# P06_USB.net
KiCad netlist of a schematic drawn in Altium Designer
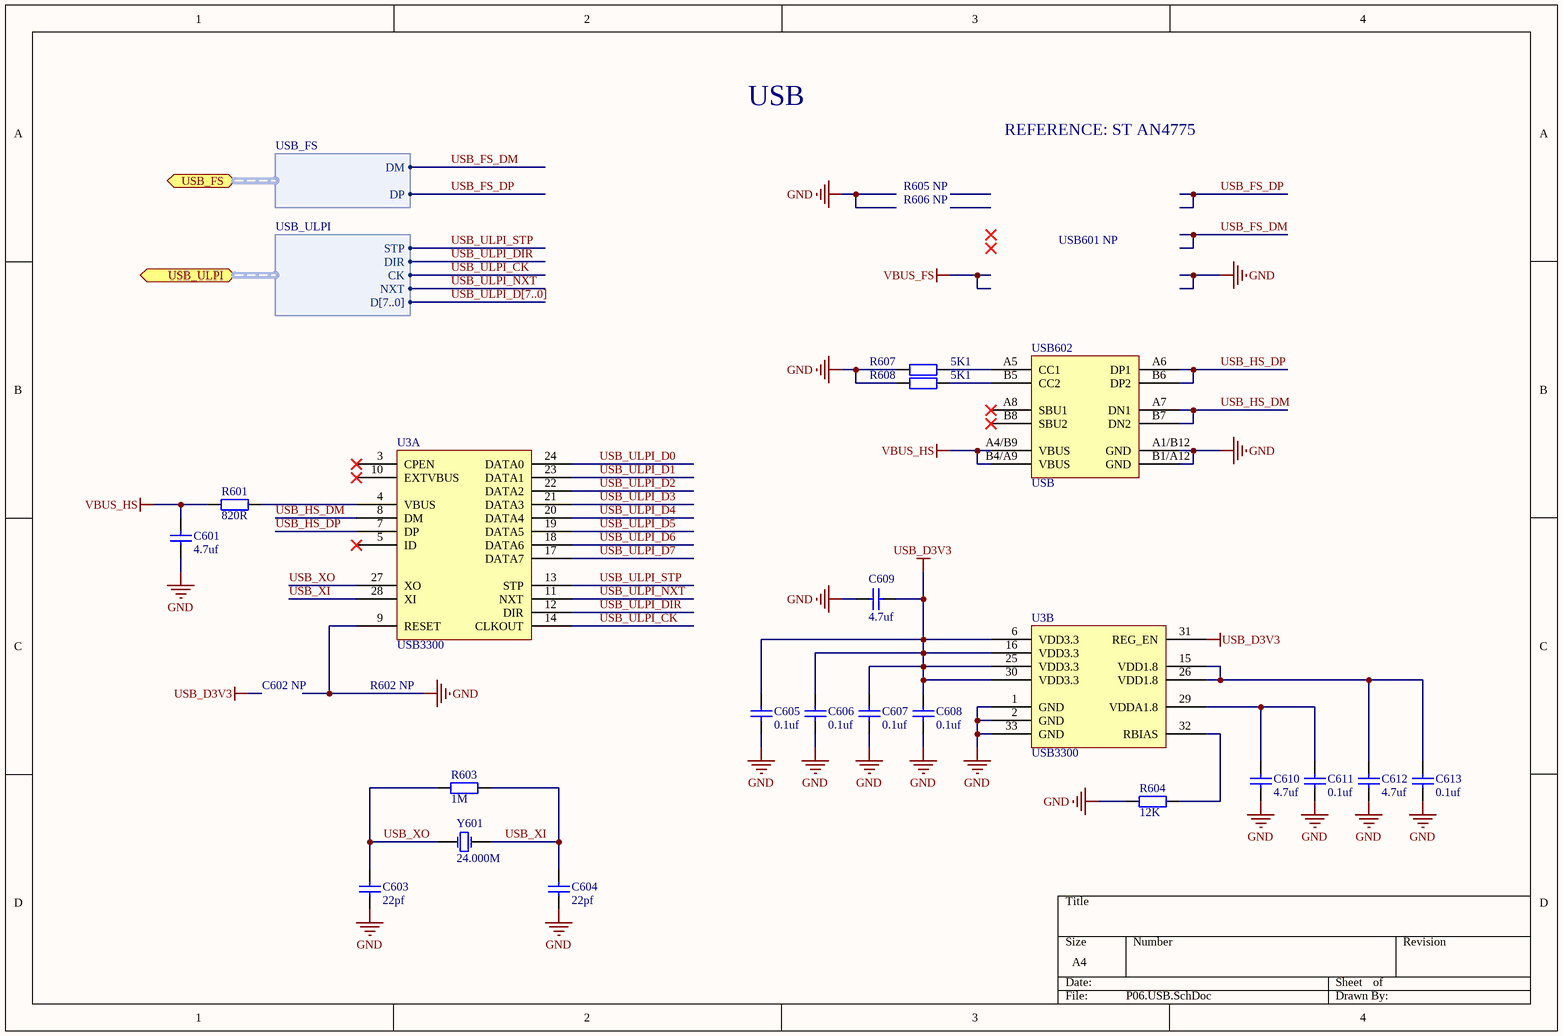
[diagram p0: P06.USB.SchDoc]

(export (version "E")
  (design (tool "Eeschema 10.0.6"))
  (components
    (comp (ref "C601")
      (value "4.7uf")
      (footprint "C0603")
      (fields (field (name "Comment") "Cap"))
      (libsource (lib "carrot_lib") (part "Cap"))
    )
    (comp (ref "C603")
      (value "22pf")
      (footprint "C0603")
      (fields (field (name "Comment") "Cap"))
      (libsource (lib "carrot_lib") (part "Cap"))
    )
    (comp (ref "C604")
      (value "22pf")
      (footprint "C0603")
      (fields (field (name "Comment") "Cap"))
      (libsource (lib "carrot_lib") (part "Cap"))
    )
    (comp (ref "C605")
      (value "0.1uf")
      (footprint "C0402")
      (fields (field (name "Comment") "Cap"))
      (libsource (lib "carrot_lib") (part "Cap"))
    )
    (comp (ref "C606")
      (value "0.1uf")
      (footprint "C0402")
      (fields (field (name "Comment") "Cap"))
      (libsource (lib "carrot_lib") (part "Cap"))
    )
    (comp (ref "C607")
      (value "0.1uf")
      (footprint "C0402")
      (fields (field (name "Comment") "Cap"))
      (libsource (lib "carrot_lib") (part "Cap"))
    )
    (comp (ref "C608")
      (value "0.1uf")
      (footprint "C0402")
      (fields (field (name "Comment") "Cap"))
      (libsource (lib "carrot_lib") (part "Cap"))
    )
    (comp (ref "C609")
      (value "4.7uf")
      (footprint "C0603")
      (fields (field (name "Comment") "Cap"))
      (libsource (lib "carrot_lib") (part "Cap"))
    )
    (comp (ref "C610")
      (value "4.7uf")
      (footprint "C0402")
      (fields (field (name "Comment") "Cap"))
      (libsource (lib "carrot_lib") (part "Cap"))
    )
    (comp (ref "C611")
      (value "0.1uf")
      (footprint "C0402")
      (fields (field (name "Comment") "Cap"))
      (libsource (lib "carrot_lib") (part "Cap"))
    )
    (comp (ref "C612")
      (value "4.7uf")
      (footprint "C0402")
      (fields (field (name "Comment") "Cap"))
      (libsource (lib "carrot_lib") (part "Cap"))
    )
    (comp (ref "C613")
      (value "0.1uf")
      (footprint "C0402")
      (fields (field (name "Comment") "Cap"))
      (libsource (lib "carrot_lib") (part "Cap"))
    )
    (comp (ref "R601")
      (value "820R")
      (footprint "R0603")
      (description "电阻")
      (fields (field (name "Comment") "Res"))
      (libsource (lib "carrot_lib") (part "Res"))
    )
    (comp (ref "R603")
      (value "1M")
      (footprint "R0603")
      (description "电阻")
      (fields (field (name "Comment") "Res"))
      (libsource (lib "carrot_lib") (part "Res"))
    )
    (comp (ref "R604")
      (value "12K")
      (footprint "R0603")
      (description "电阻")
      (fields (field (name "Comment") "Res"))
      (libsource (lib "carrot_lib") (part "Res"))
    )
    (comp (ref "R607")
      (value "5K1")
      (footprint "R0603")
      (description "电阻")
      (fields (field (name "Comment") "Res"))
      (libsource (lib "carrot_lib") (part "Res"))
    )
    (comp (ref "R608")
      (value "5K1")
      (footprint "R0603")
      (description "电阻")
      (fields (field (name "Comment") "Res"))
      (libsource (lib "carrot_lib") (part "Res"))
    )
    (comp (ref "U3")
      (value "USB3300")
      (footprint "USB3300-QFN32")
      (description "Hi-Speed USB Host, Device or OTG PHY with ULPI Low Pin Interface")
      (libsource (lib "carrot_lib") (part "USB3300"))
    )
    (comp (ref "USB602")
      (value "USB")
      (footprint "USB-TYPEC-F-16P-THD")
      (libsource (lib "carrot_lib") (part "USB3"))
    )
    (comp (ref "Y601")
      (value "24.000M")
      (footprint "XTAL-3225")
      (description "Crystal Oscillator")
      (fields (field (name "Comment") "XTAL"))
      (libsource (lib "carrot_lib") (part "XTAL3"))
    )
  )
  (nets
    (net (code "5") (name "/USB_HS_DM") (class "Default")
      (node (ref "U3") (pin "8") (pinfunction "DM_8") (pintype "passive"))
      (node (ref "USB602") (pin "A7") (pinfunction "DN1_A7") (pintype "passive"))
      (node (ref "USB602") (pin "B7") (pinfunction "DN2_B7") (pintype "passive"))
    )
    (net (code "6") (name "/USB_HS_DP") (class "Default")
      (node (ref "U3") (pin "7") (pinfunction "DP_7") (pintype "passive"))
      (node (ref "USB602") (pin "A6") (pinfunction "DP1_A6") (pintype "passive"))
      (node (ref "USB602") (pin "B6") (pinfunction "DP2_B6") (pintype "passive"))
    )
    (net (code "7") (name "/USB_ULPI_CK") (class "Default")
      (node (ref "U3") (pin "14") (pinfunction "CLKOUT_14") (pintype "passive"))
    )
    (net (code "8") (name "/USB_ULPI_D0") (class "Default")
      (node (ref "U3") (pin "24") (pinfunction "DATA0_24") (pintype "passive"))
    )
    (net (code "9") (name "/USB_ULPI_D1") (class "Default")
      (node (ref "U3") (pin "23") (pinfunction "DATA1_23") (pintype "passive"))
    )
    (net (code "10") (name "/USB_ULPI_D2") (class "Default")
      (node (ref "U3") (pin "22") (pinfunction "DATA2_22") (pintype "passive"))
    )
    (net (code "11") (name "/USB_ULPI_D3") (class "Default")
      (node (ref "U3") (pin "21") (pinfunction "DATA3_21") (pintype "passive"))
    )
    (net (code "12") (name "/USB_ULPI_D4") (class "Default")
      (node (ref "U3") (pin "20") (pinfunction "DATA4_20") (pintype "passive"))
    )
    (net (code "13") (name "/USB_ULPI_D5") (class "Default")
      (node (ref "U3") (pin "19") (pinfunction "DATA5_19") (pintype "passive"))
    )
    (net (code "14") (name "/USB_ULPI_D6") (class "Default")
      (node (ref "U3") (pin "18") (pinfunction "DATA6_18") (pintype "passive"))
    )
    (net (code "15") (name "/USB_ULPI_D7") (class "Default")
      (node (ref "U3") (pin "17") (pinfunction "DATA7_17") (pintype "passive"))
    )
    (net (code "16") (name "/USB_ULPI_DIR") (class "Default")
      (node (ref "U3") (pin "12") (pinfunction "DIR_12") (pintype "passive"))
    )
    (net (code "17") (name "/USB_ULPI_NXT") (class "Default")
      (node (ref "U3") (pin "11") (pinfunction "NXT_11") (pintype "passive"))
    )
    (net (code "18") (name "/USB_ULPI_STP") (class "Default")
      (node (ref "U3") (pin "13") (pinfunction "STP_13") (pintype "passive"))
    )
    (net (code "20") (name "/USB_XI") (class "Default")
      (node (ref "C604") (pin "2") (pinfunction "2_2") (pintype "passive"))
      (node (ref "R603") (pin "2") (pinfunction "2_2") (pintype "passive"))
      (node (ref "U3") (pin "28") (pinfunction "XI_28") (pintype "passive"))
      (node (ref "Y601") (pin "3") (pinfunction "OSC2_3") (pintype "passive"))
    )
    (net (code "21") (name "/USB_XO") (class "Default")
      (node (ref "C603") (pin "2") (pinfunction "2_2") (pintype "passive"))
      (node (ref "R603") (pin "1") (pinfunction "1_1") (pintype "passive"))
      (node (ref "U3") (pin "27") (pinfunction "XO_27") (pintype "passive"))
      (node (ref "Y601") (pin "1") (pinfunction "OSC1_1") (pintype "passive"))
    )
    (net (code "24") (name "GND") (class "Default")
      (node (ref "C601") (pin "1") (pinfunction "1_1") (pintype "passive"))
      (node (ref "C603") (pin "1") (pinfunction "1_1") (pintype "passive"))
      (node (ref "C604") (pin "1") (pinfunction "1_1") (pintype "passive"))
      (node (ref "C605") (pin "1") (pinfunction "1_1") (pintype "passive"))
      (node (ref "C606") (pin "1") (pinfunction "1_1") (pintype "passive"))
      (node (ref "C607") (pin "1") (pinfunction "1_1") (pintype "passive"))
      (node (ref "C608") (pin "1") (pinfunction "1_1") (pintype "passive"))
      (node (ref "C609") (pin "1") (pinfunction "1_1") (pintype "passive"))
      (node (ref "C610") (pin "1") (pinfunction "1_1") (pintype "passive"))
      (node (ref "C611") (pin "1") (pinfunction "1_1") (pintype "passive"))
      (node (ref "C612") (pin "1") (pinfunction "1_1") (pintype "passive"))
      (node (ref "C613") (pin "1") (pinfunction "1_1") (pintype "passive"))
      (node (ref "R604") (pin "1") (pinfunction "1_1") (pintype "passive"))
      (node (ref "R607") (pin "1") (pinfunction "1_1") (pintype "passive"))
      (node (ref "R608") (pin "1") (pinfunction "1_1") (pintype "passive"))
      (node (ref "U3") (pin "1") (pinfunction "GND_1") (pintype "passive"))
      (node (ref "U3") (pin "2") (pinfunction "GND_2") (pintype "passive"))
      (node (ref "U3") (pin "33") (pinfunction "GND_33") (pintype "passive"))
      (node (ref "U3") (pin "9") (pinfunction "RESET_9") (pintype "passive"))
      (node (ref "USB602") (pin "A1/B12") (pinfunction "GND_A1/B12") (pintype "passive"))
      (node (ref "USB602") (pin "B1/A12") (pinfunction "GND_B1/A12") (pintype "passive"))
    )
    (net (code "25") (name "Net-(C612-Pad2)") (class "Default")
      (node (ref "C612") (pin "2") (pinfunction "2_2") (pintype "passive"))
      (node (ref "C613") (pin "2") (pinfunction "2_2") (pintype "passive"))
      (node (ref "U3") (pin "15") (pinfunction "VDD1.8_15") (pintype "passive"))
      (node (ref "U3") (pin "26") (pinfunction "VDD1.8_26") (pintype "passive"))
    )
    (net (code "26") (name "Net-(U3A-VBUS)") (class "Default")
      (node (ref "R601") (pin "2") (pinfunction "2_2") (pintype "passive"))
      (node (ref "U3") (pin "4") (pinfunction "VBUS_4") (pintype "passive"))
    )
    (net (code "27") (name "Net-(U3B-RBIAS)") (class "Default")
      (node (ref "R604") (pin "2") (pinfunction "2_2") (pintype "passive"))
      (node (ref "U3") (pin "32") (pinfunction "RBIAS_32") (pintype "passive"))
    )
    (net (code "28") (name "Net-(U3B-VDDA1.8)") (class "Default")
      (node (ref "C610") (pin "2") (pinfunction "2_2") (pintype "passive"))
      (node (ref "C611") (pin "2") (pinfunction "2_2") (pintype "passive"))
      (node (ref "U3") (pin "29") (pinfunction "VDDA1.8_29") (pintype "passive"))
    )
    (net (code "29") (name "Net-(USB602-CC1)") (class "Default")
      (node (ref "R607") (pin "2") (pinfunction "2_2") (pintype "passive"))
      (node (ref "USB602") (pin "A5") (pinfunction "CC1_A5") (pintype "passive"))
    )
    (net (code "30") (name "Net-(USB602-CC2)") (class "Default")
      (node (ref "R608") (pin "2") (pinfunction "2_2") (pintype "passive"))
      (node (ref "USB602") (pin "B5") (pinfunction "CC2_B5") (pintype "passive"))
    )
    (net (code "31") (name "USB_D3V3") (class "Default")
      (node (ref "C605") (pin "2") (pinfunction "2_2") (pintype "passive"))
      (node (ref "C606") (pin "2") (pinfunction "2_2") (pintype "passive"))
      (node (ref "C607") (pin "2") (pinfunction "2_2") (pintype "passive"))
      (node (ref "C608") (pin "2") (pinfunction "2_2") (pintype "passive"))
      (node (ref "C609") (pin "2") (pinfunction "2_2") (pintype "passive"))
      (node (ref "U3") (pin "16") (pinfunction "VDD3.3_16") (pintype "passive"))
      (node (ref "U3") (pin "25") (pinfunction "VDD3.3_25") (pintype "passive"))
      (node (ref "U3") (pin "30") (pinfunction "VDD3.3_30") (pintype "passive"))
      (node (ref "U3") (pin "31") (pinfunction "REG_EN_31") (pintype "passive"))
      (node (ref "U3") (pin "6") (pinfunction "VDD3.3_6") (pintype "passive"))
    )
    (net (code "33") (name "VBUS_HS") (class "Default")
      (node (ref "C601") (pin "2") (pinfunction "2_2") (pintype "passive"))
      (node (ref "R601") (pin "1") (pinfunction "1_1") (pintype "passive"))
      (node (ref "USB602") (pin "A4/B9") (pinfunction "VBUS_A4/B9") (pintype "passive"))
      (node (ref "USB602") (pin "B4/A9") (pinfunction "VBUS_B4/A9") (pintype "passive"))
    )
    (net (code "34") (name "unconnected-(U3A-CPEN-Pad3)") (class "Default")
      (node (ref "U3") (pin "3") (pinfunction "CPEN_3") (pintype "passive+no_connect"))
    )
    (net (code "35") (name "unconnected-(U3A-EXTVBUS-Pad10)") (class "Default")
      (node (ref "U3") (pin "10") (pinfunction "EXTVBUS_10") (pintype "passive+no_connect"))
    )
    (net (code "36") (name "unconnected-(U3A-ID-Pad5)") (class "Default")
      (node (ref "U3") (pin "5") (pinfunction "ID_5") (pintype "passive+no_connect"))
    )
    (net (code "37") (name "unconnected-(USB602-SBU1-PadA8)") (class "Default")
      (node (ref "USB602") (pin "A8") (pinfunction "SBU1_A8") (pintype "passive+no_connect"))
    )
    (net (code "38") (name "unconnected-(USB602-SBU2-PadB8)") (class "Default")
      (node (ref "USB602") (pin "B8") (pinfunction "SBU2_B8") (pintype "passive+no_connect"))
    )
  )
)
